# CANode.net
KiCad netlist of a schematic drawn in EAGLE
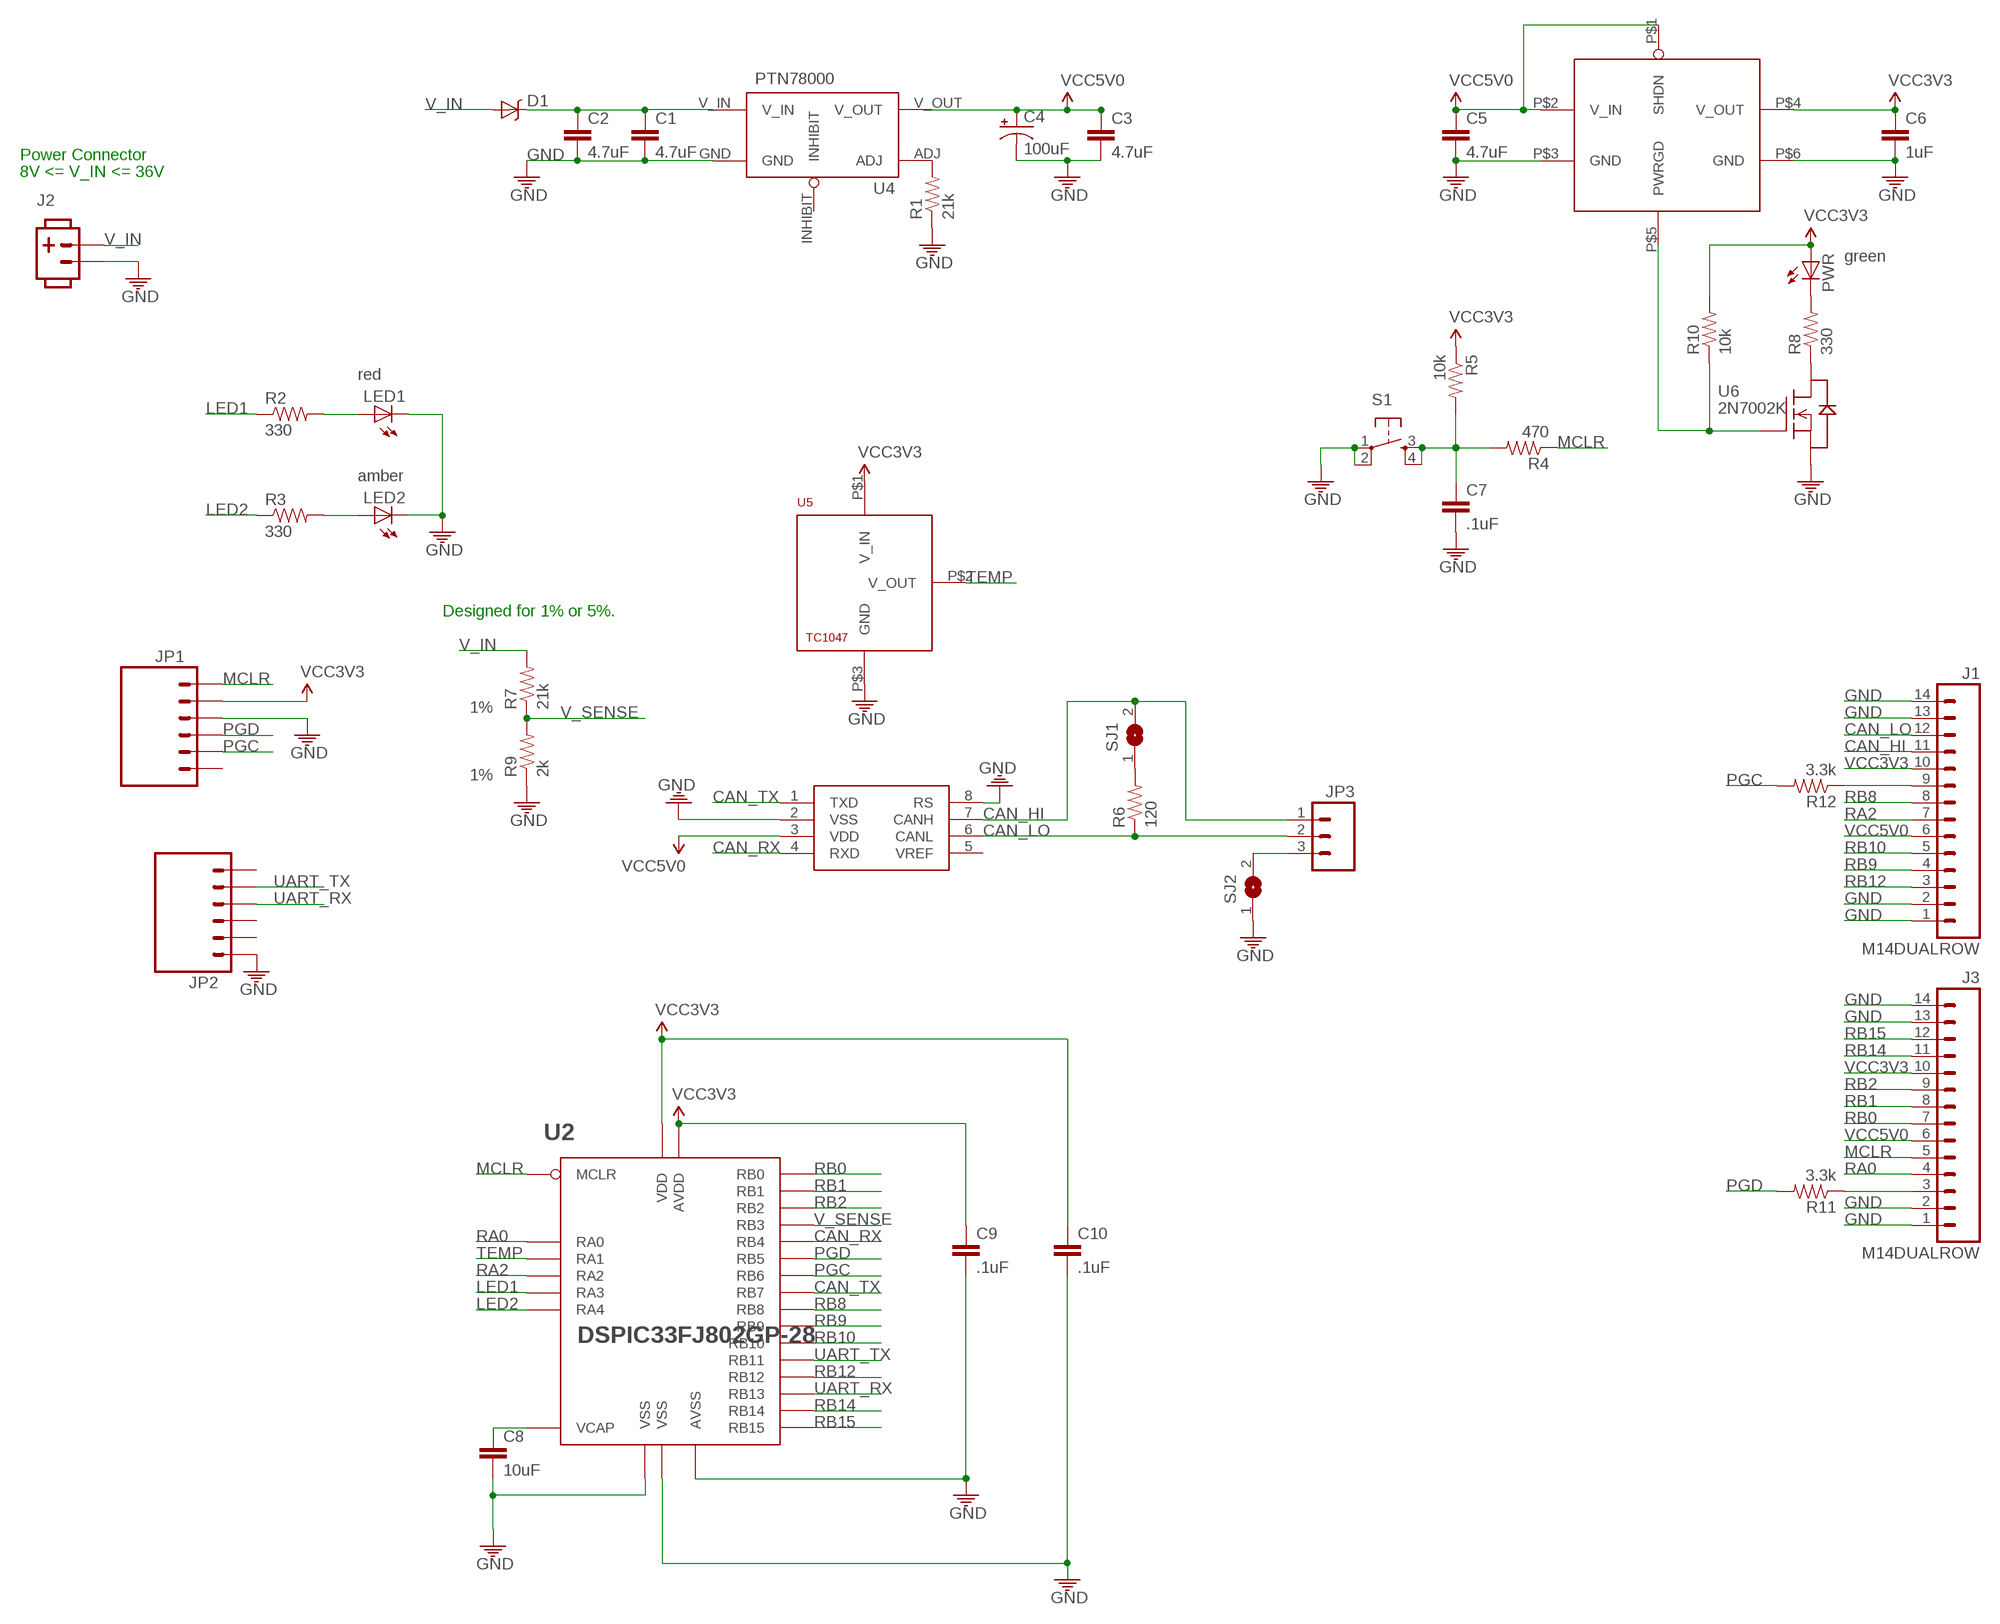
[diagram p0: schematic, sheet 1]

(export (version "E")
  (design (tool "Eeschema 10.0.6"))
  (components
    (comp (ref "C1")
      (value "4.7uF")
      (footprint "eagle-import:1206")
      (libsource (lib "eagle-import") (part "CAP1206"))
    )
    (comp (ref "C2")
      (value "4.7uF")
      (footprint "eagle-import:1206")
      (libsource (lib "eagle-import") (part "CAP1206"))
    )
    (comp (ref "C3")
      (value "4.7uF")
      (footprint "eagle-import:1206")
      (libsource (lib "eagle-import") (part "CAP1206"))
    )
    (comp (ref "C4")
      (value "100uF")
      (footprint "eagle-import:CPOL-RADIAL-100UF-25V")
      (libsource (lib "eagle-import") (part "CAP_POLPTH1"))
    )
    (comp (ref "C5")
      (value "4.7uF")
      (footprint "eagle-import:1206")
      (libsource (lib "eagle-import") (part "CAP1206"))
    )
    (comp (ref "C6")
      (value "1uF")
      (footprint "eagle-import:1206")
      (libsource (lib "eagle-import") (part "CAP1206"))
    )
    (comp (ref "C7")
      (value ".1uF")
      (footprint "eagle-import:1206")
      (libsource (lib "eagle-import") (part "CAP1206"))
    )
    (comp (ref "C8")
      (value "10uF")
      (footprint "eagle-import:1206")
      (libsource (lib "eagle-import") (part "CAP1206"))
    )
    (comp (ref "C9")
      (value ".1uF")
      (footprint "eagle-import:1206")
      (libsource (lib "eagle-import") (part "CAP1206"))
    )
    (comp (ref "C10")
      (value ".1uF")
      (footprint "eagle-import:1206")
      (libsource (lib "eagle-import") (part "CAP1206"))
    )
    (comp (ref "D1")
      (value "DIODE-SCHOTTKY240A")
      (footprint "eagle-import:SMA-DIODE-B240A")
      (libsource (lib "eagle-import") (part "DIODE-SCHOTTKY240A"))
    )
    (comp (ref "J1")
      (value "M14DUALROW")
      (footprint "eagle-import:2X7")
      (libsource (lib "eagle-import") (part "M14DUALROW"))
    )
    (comp (ref "J2")
      (value "POW_CONNECTMALE-RA")
      (footprint "eagle-import:SOCKET-MALE_RA-3.96MM-2")
      (libsource (lib "eagle-import") (part "POW_CONNECTMALE-RA"))
    )
    (comp (ref "J3")
      (value "M14DUALROW")
      (footprint "eagle-import:2X7")
      (libsource (lib "eagle-import") (part "M14DUALROW"))
    )
    (comp (ref "JP1")
      (value "M06RA_LOCK")
      (footprint "eagle-import:MOLEX-1X6-RA_LOCK")
      (libsource (lib "eagle-import") (part "M06RA_LOCK"))
    )
    (comp (ref "JP2")
      (value "M06LOCK")
      (footprint "eagle-import:1X06_LOCK")
      (libsource (lib "eagle-import") (part "CMPE118lib_M06LOCK"))
    )
    (comp (ref "JP3")
      (value "M03LOCK")
      (footprint "eagle-import:1X03_LOCK")
      (libsource (lib "eagle-import") (part "M03LOCK"))
    )
    (comp (ref "LED1")
      (value "LED1206")
      (footprint "eagle-import:LED-1206")
      (fields (field (name "COLOR") "red"))
      (libsource (lib "eagle-import") (part "LED1206"))
    )
    (comp (ref "LED2")
      (value "LED1206")
      (footprint "eagle-import:LED-1206")
      (fields (field (name "COLOR") "amber"))
      (libsource (lib "eagle-import") (part "LED1206"))
    )
    (comp (ref "PWR")
      (value "LED1206")
      (footprint "eagle-import:LED-1206")
      (fields (field (name "COLOR") "green"))
      (libsource (lib "eagle-import") (part "LED1206"))
    )
    (comp (ref "R1")
      (value "21k")
      (footprint "eagle-import:0805")
      (libsource (lib "eagle-import") (part "RESISTOR0805-RES"))
    )
    (comp (ref "R2")
      (value "330")
      (footprint "eagle-import:0805")
      (libsource (lib "eagle-import") (part "RESISTOR0805-RES"))
    )
    (comp (ref "R3")
      (value "330")
      (footprint "eagle-import:0805")
      (libsource (lib "eagle-import") (part "RESISTOR0805-RES"))
    )
    (comp (ref "R4")
      (value "470")
      (footprint "eagle-import:0805")
      (libsource (lib "eagle-import") (part "RESISTOR0805-RES"))
    )
    (comp (ref "R5")
      (value "10k")
      (footprint "eagle-import:0805")
      (libsource (lib "eagle-import") (part "RESISTOR0805-RES"))
    )
    (comp (ref "R6")
      (value "120")
      (footprint "eagle-import:0805")
      (libsource (lib "eagle-import") (part "RESISTOR0805-RES"))
    )
    (comp (ref "R7")
      (value "21k")
      (footprint "eagle-import:0805")
      (fields (field (name "PRECISION") "1%"))
      (libsource (lib "eagle-import") (part "RESISTOR0805-RES"))
    )
    (comp (ref "R8")
      (value "330")
      (footprint "eagle-import:0805")
      (libsource (lib "eagle-import") (part "RESISTOR0805-RES"))
    )
    (comp (ref "R9")
      (value "2k")
      (footprint "eagle-import:0805")
      (fields (field (name "PRECISION") "1%"))
      (libsource (lib "eagle-import") (part "RESISTOR0805-RES"))
    )
    (comp (ref "R10")
      (value "10k")
      (footprint "eagle-import:0805")
      (libsource (lib "eagle-import") (part "RESISTOR0805-RES"))
    )
    (comp (ref "R11")
      (value "3.3k")
      (footprint "eagle-import:0805")
      (libsource (lib "eagle-import") (part "RESISTOR0805-RES"))
    )
    (comp (ref "R12")
      (value "3.3k")
      (footprint "eagle-import:0805")
      (libsource (lib "eagle-import") (part "RESISTOR0805-RES"))
    )
    (comp (ref "S1")
      (value "TAC_SWITCHPTH")
      (footprint "eagle-import:B3F-1020")
      (libsource (lib "eagle-import") (part "TAC_SWITCHPTH"))
    )
    (comp (ref "SJ1") (value "SJ") (footprint "eagle-import:SJ") (libsource (lib "eagle-import") (part "SJ")))
    (comp (ref "SJ2") (value "SJ") (footprint "eagle-import:SJ") (libsource (lib "eagle-import") (part "SJ")))
    (comp (ref "U1")
      (value "MCP2551")
      (footprint "eagle-import:SO08")
      (libsource (lib "eagle-import") (part "MCP2551"))
    )
    (comp (ref "U2")
      (value "DSPIC33FJ802GP-28")
      (footprint "eagle-import:SOIC28-W")
      (libsource (lib "eagle-import") (part "DSPIC33FJ802GP-28"))
    )
    (comp (ref "U3")
      (value "MCP1826")
      (footprint "eagle-import:SOT223-5")
      (libsource (lib "eagle-import") (part "MCP1826"))
    )
    (comp (ref "U4")
      (value "PTN78000")
      (footprint "eagle-import:PTN78000")
      (libsource (lib "eagle-import") (part "PTN78000THROUGH-HOLE"))
    )
    (comp (ref "U5")
      (value "TC1047")
      (footprint "eagle-import:SOT-23B")
      (libsource (lib "eagle-import") (part "TC1047"))
    )
    (comp (ref "U6")
      (value "2N7002K")
      (footprint "eagle-import:SOT23-3")
      (libsource (lib "eagle-import") (part "2N7002K"))
    )
  )
  (nets
    (net (code "1") (name "/CAN_HI") (class "Default")
      (node (ref "J1") (pin "11") (pinfunction "11_11") (pintype "passive"))
      (node (ref "JP3") (pin "1") (pinfunction "1_1") (pintype "passive"))
      (node (ref "SJ1") (pin "2") (pinfunction "2_2") (pintype "passive"))
      (node (ref "U1") (pin "7") (pinfunction "CANH_7") (pintype "bidirectional"))
    )
    (net (code "2") (name "/CAN_LO") (class "Default")
      (node (ref "J1") (pin "12") (pinfunction "12_12") (pintype "passive"))
      (node (ref "JP3") (pin "2") (pinfunction "2_2") (pintype "passive"))
      (node (ref "R6") (pin "1") (pinfunction "1_1") (pintype "passive"))
      (node (ref "U1") (pin "6") (pinfunction "CANL_6") (pintype "bidirectional"))
    )
    (net (code "3") (name "/CAN_RX") (class "Default")
      (node (ref "U1") (pin "4") (pinfunction "RXD_4") (pintype "bidirectional"))
      (node (ref "U2") (pin "P$11") (pinfunction "RB4_P$11") (pintype "bidirectional"))
    )
    (net (code "4") (name "/CAN_TX") (class "Default")
      (node (ref "U1") (pin "1") (pinfunction "TXD_1") (pintype "bidirectional"))
      (node (ref "U2") (pin "P$16") (pinfunction "RB7_P$16") (pintype "bidirectional"))
    )
    (net (code "5") (name "/LED1") (class "Default")
      (node (ref "R2") (pin "1") (pinfunction "1_1") (pintype "passive"))
      (node (ref "U2") (pin "P$10") (pinfunction "RA3_P$10") (pintype "bidirectional"))
    )
    (net (code "6") (name "/LED2") (class "Default")
      (node (ref "R3") (pin "1") (pinfunction "1_1") (pintype "passive"))
      (node (ref "U2") (pin "P$12") (pinfunction "RA4_P$12") (pintype "bidirectional"))
    )
    (net (code "7") (name "/MCLR") (class "Default")
      (node (ref "J3") (pin "5") (pinfunction "5_5") (pintype "passive"))
      (node (ref "JP1") (pin "1") (pinfunction "1_1") (pintype "passive"))
      (node (ref "R4") (pin "1") (pinfunction "1_1") (pintype "passive"))
      (node (ref "U2") (pin "P$1") (pinfunction "MCLR_P$1") (pintype "bidirectional"))
    )
    (net (code "8") (name "/PGC") (class "Default")
      (node (ref "JP1") (pin "5") (pinfunction "5_5") (pintype "passive"))
      (node (ref "R12") (pin "2") (pinfunction "2_2") (pintype "passive"))
      (node (ref "U2") (pin "P$15") (pinfunction "RB6_P$15") (pintype "bidirectional"))
    )
    (net (code "9") (name "/PGD") (class "Default")
      (node (ref "JP1") (pin "4") (pinfunction "4_4") (pintype "passive"))
      (node (ref "R11") (pin "2") (pinfunction "2_2") (pintype "passive"))
      (node (ref "U2") (pin "P$14") (pinfunction "RB5_P$14") (pintype "bidirectional"))
    )
    (net (code "10") (name "/RA0") (class "Default")
      (node (ref "J3") (pin "4") (pinfunction "4_4") (pintype "passive"))
      (node (ref "U2") (pin "P$2") (pinfunction "RA0_P$2") (pintype "bidirectional"))
    )
    (net (code "11") (name "/RA2") (class "Default")
      (node (ref "J1") (pin "7") (pinfunction "7_7") (pintype "passive"))
      (node (ref "U2") (pin "P$9") (pinfunction "RA2_P$9") (pintype "bidirectional"))
    )
    (net (code "12") (name "/RB0") (class "Default")
      (node (ref "J3") (pin "7") (pinfunction "7_7") (pintype "passive"))
      (node (ref "U2") (pin "P$4") (pinfunction "RB0_P$4") (pintype "bidirectional"))
    )
    (net (code "13") (name "/RB1") (class "Default")
      (node (ref "J3") (pin "8") (pinfunction "8_8") (pintype "passive"))
      (node (ref "U2") (pin "P$5") (pinfunction "RB1_P$5") (pintype "bidirectional"))
    )
    (net (code "14") (name "/RB2") (class "Default")
      (node (ref "J3") (pin "9") (pinfunction "9_9") (pintype "passive"))
      (node (ref "U2") (pin "P$6") (pinfunction "RB2_P$6") (pintype "bidirectional"))
    )
    (net (code "15") (name "/RB8") (class "Default")
      (node (ref "J1") (pin "8") (pinfunction "8_8") (pintype "passive"))
      (node (ref "U2") (pin "P$17") (pinfunction "RB8_P$17") (pintype "bidirectional"))
    )
    (net (code "16") (name "/RB9") (class "Default")
      (node (ref "J1") (pin "4") (pinfunction "4_4") (pintype "passive"))
      (node (ref "U2") (pin "P$18") (pinfunction "RB9_P$18") (pintype "bidirectional"))
    )
    (net (code "17") (name "/RB10") (class "Default")
      (node (ref "J1") (pin "5") (pinfunction "5_5") (pintype "passive"))
      (node (ref "U2") (pin "P$21") (pinfunction "RB10_P$21") (pintype "bidirectional"))
    )
    (net (code "18") (name "/RB12") (class "Default")
      (node (ref "J1") (pin "3") (pinfunction "3_3") (pintype "passive"))
      (node (ref "U2") (pin "P$23") (pinfunction "RB12_P$23") (pintype "bidirectional"))
    )
    (net (code "19") (name "/RB14") (class "Default")
      (node (ref "J3") (pin "11") (pinfunction "11_11") (pintype "passive"))
      (node (ref "U2") (pin "P$25") (pinfunction "RB14_P$25") (pintype "bidirectional"))
    )
    (net (code "20") (name "/RB15") (class "Default")
      (node (ref "J3") (pin "12") (pinfunction "12_12") (pintype "passive"))
      (node (ref "U2") (pin "P$26") (pinfunction "RB15_P$26") (pintype "bidirectional"))
    )
    (net (code "21") (name "/TEMP") (class "Default")
      (node (ref "U2") (pin "P$3") (pinfunction "RA1_P$3") (pintype "bidirectional"))
      (node (ref "U5") (pin "P$2") (pinfunction "V_OUT_P$2") (pintype "output"))
    )
    (net (code "22") (name "/UART_RX") (class "Default")
      (node (ref "JP2") (pin "4") (pinfunction "4_4") (pintype "passive"))
      (node (ref "U2") (pin "P$24") (pinfunction "RB13_P$24") (pintype "bidirectional"))
    )
    (net (code "23") (name "/UART_TX") (class "Default")
      (node (ref "JP2") (pin "5") (pinfunction "5_5") (pintype "passive"))
      (node (ref "U2") (pin "P$22") (pinfunction "RB11_P$22") (pintype "bidirectional"))
    )
    (net (code "24") (name "/V_IN") (class "Default")
      (node (ref "D1") (pin "A") (pinfunction "A_A") (pintype "passive"))
      (node (ref "J2") (pin "1") (pinfunction "1_1") (pintype "passive"))
      (node (ref "R7") (pin "2") (pinfunction "2_2") (pintype "passive"))
    )
    (net (code "25") (name "/V_SENSE") (class "Default")
      (node (ref "R7") (pin "1") (pinfunction "1_1") (pintype "passive"))
      (node (ref "R9") (pin "2") (pinfunction "2_2") (pintype "passive"))
      (node (ref "U2") (pin "P$7") (pinfunction "RB3_P$7") (pintype "bidirectional"))
    )
    (net (code "26") (name "GND") (class "Default")
      (node (ref "C1") (pin "2") (pinfunction "2_2") (pintype "passive"))
      (node (ref "C10") (pin "2") (pinfunction "2_2") (pintype "passive"))
      (node (ref "C2") (pin "2") (pinfunction "2_2") (pintype "passive"))
      (node (ref "C3") (pin "2") (pinfunction "2_2") (pintype "passive"))
      (node (ref "C4") (pin "2") (pinfunction "-_2") (pintype "passive"))
      (node (ref "C5") (pin "2") (pinfunction "2_2") (pintype "passive"))
      (node (ref "C6") (pin "2") (pinfunction "2_2") (pintype "passive"))
      (node (ref "C7") (pin "2") (pinfunction "2_2") (pintype "passive"))
      (node (ref "C8") (pin "2") (pinfunction "2_2") (pintype "passive"))
      (node (ref "C9") (pin "2") (pinfunction "2_2") (pintype "passive"))
      (node (ref "J1") (pin "1") (pinfunction "1_1") (pintype "passive"))
      (node (ref "J1") (pin "13") (pinfunction "13_13") (pintype "passive"))
      (node (ref "J1") (pin "14") (pinfunction "14_14") (pintype "passive"))
      (node (ref "J1") (pin "2") (pinfunction "2_2") (pintype "passive"))
      (node (ref "J2") (pin "2") (pinfunction "2_2") (pintype "passive"))
      (node (ref "J3") (pin "1") (pinfunction "1_1") (pintype "passive"))
      (node (ref "J3") (pin "13") (pinfunction "13_13") (pintype "passive"))
      (node (ref "J3") (pin "14") (pinfunction "14_14") (pintype "passive"))
      (node (ref "J3") (pin "2") (pinfunction "2_2") (pintype "passive"))
      (node (ref "JP1") (pin "3") (pinfunction "3_3") (pintype "passive"))
      (node (ref "JP2") (pin "1") (pinfunction "1_1") (pintype "passive"))
      (node (ref "LED1") (pin "C") (pinfunction "C_C") (pintype "passive"))
      (node (ref "LED2") (pin "C") (pinfunction "C_C") (pintype "passive"))
      (node (ref "R1") (pin "1") (pinfunction "1_1") (pintype "passive"))
      (node (ref "R9") (pin "1") (pinfunction "1_1") (pintype "passive"))
      (node (ref "S1") (pin "1") (pinfunction "1_1") (pintype "passive"))
      (node (ref "S1") (pin "2") (pinfunction "2_2") (pintype "passive"))
      (node (ref "SJ2") (pin "1") (pinfunction "1_1") (pintype "passive"))
      (node (ref "U1") (pin "2") (pinfunction "VSS_2") (pintype "bidirectional"))
      (node (ref "U1") (pin "8") (pinfunction "RS_8") (pintype "bidirectional"))
      (node (ref "U2") (pin "P$19") (pinfunction "VSS_P$19") (pintype "power_in"))
      (node (ref "U2") (pin "P$27") (pinfunction "AVSS_P$27") (pintype "input"))
      (node (ref "U2") (pin "P$8") (pinfunction "VSS_P$8") (pintype "power_in"))
      (node (ref "U3") (pin "P$3") (pinfunction "GND_P$3") (pintype "power_in"))
      (node (ref "U3") (pin "P$6") (pinfunction "GND_P$6") (pintype "power_in"))
      (node (ref "U4") (pin "GND") (pinfunction "GND_GND") (pintype "power_in"))
      (node (ref "U5") (pin "P$3") (pinfunction "GND_P$3") (pintype "power_in"))
      (node (ref "U6") (pin "2") (pinfunction "S_2") (pintype "passive"))
    )
    (net (code "27") (name "Net-(C1-Pad1)") (class "Default")
      (node (ref "C1") (pin "1") (pinfunction "1_1") (pintype "passive"))
      (node (ref "C2") (pin "1") (pinfunction "1_1") (pintype "passive"))
      (node (ref "D1") (pin "C") (pinfunction "C_C") (pintype "passive"))
      (node (ref "U4") (pin "V_IN") (pinfunction "V_IN_V_IN") (pintype "power_in"))
    )
    (net (code "28") (name "Net-(C7-Pad1)") (class "Default")
      (node (ref "C7") (pin "1") (pinfunction "1_1") (pintype "passive"))
      (node (ref "R4") (pin "2") (pinfunction "2_2") (pintype "passive"))
      (node (ref "R5") (pin "2") (pinfunction "2_2") (pintype "passive"))
      (node (ref "S1") (pin "3") (pinfunction "3_3") (pintype "passive"))
      (node (ref "S1") (pin "4") (pinfunction "4_4") (pintype "passive"))
    )
    (net (code "29") (name "Net-(J1-Pad9)") (class "Default")
      (node (ref "J1") (pin "9") (pinfunction "9_9") (pintype "passive"))
      (node (ref "R12") (pin "1") (pinfunction "1_1") (pintype "passive"))
    )
    (net (code "30") (name "Net-(J3-Pad3)") (class "Default")
      (node (ref "J3") (pin "3") (pinfunction "3_3") (pintype "passive"))
      (node (ref "R11") (pin "1") (pinfunction "1_1") (pintype "passive"))
    )
    (net (code "31") (name "Net-(JP3-Pad3)") (class "Default")
      (node (ref "JP3") (pin "3") (pinfunction "3_3") (pintype "passive"))
      (node (ref "SJ2") (pin "2") (pinfunction "2_2") (pintype "passive"))
    )
    (net (code "32") (name "Net-(LED1-PadA)") (class "Default")
      (node (ref "LED1") (pin "A") (pinfunction "A_A") (pintype "passive"))
      (node (ref "R2") (pin "2") (pinfunction "2_2") (pintype "passive"))
    )
    (net (code "33") (name "Net-(LED2-PadA)") (class "Default")
      (node (ref "LED2") (pin "A") (pinfunction "A_A") (pintype "passive"))
      (node (ref "R3") (pin "2") (pinfunction "2_2") (pintype "passive"))
    )
    (net (code "34") (name "Net-(PWR-PadC)") (class "Default")
      (node (ref "PWR") (pin "C") (pinfunction "C_C") (pintype "passive"))
      (node (ref "R8") (pin "2") (pinfunction "2_2") (pintype "passive"))
    )
    (net (code "35") (name "Net-(R1-Pad2)") (class "Default")
      (node (ref "R1") (pin "2") (pinfunction "2_2") (pintype "passive"))
      (node (ref "U4") (pin "ADJ") (pinfunction "ADJ_ADJ") (pintype "input"))
    )
    (net (code "36") (name "Net-(R6-Pad2)") (class "Default")
      (node (ref "R6") (pin "2") (pinfunction "2_2") (pintype "passive"))
      (node (ref "SJ1") (pin "1") (pinfunction "1_1") (pintype "passive"))
    )
    (net (code "37") (name "Net-(U2-VCAP)") (class "Default")
      (node (ref "C8") (pin "1") (pinfunction "1_1") (pintype "passive"))
      (node (ref "U2") (pin "P$20") (pinfunction "VCAP_P$20") (pintype "input"))
    )
    (net (code "38") (name "Net-(U3-PWRGD)") (class "Default")
      (node (ref "R10") (pin "1") (pinfunction "1_1") (pintype "passive"))
      (node (ref "U3") (pin "P$5") (pinfunction "PWRGD_P$5") (pintype "open_collector"))
      (node (ref "U6") (pin "1") (pinfunction "G_1") (pintype "passive"))
    )
    (net (code "39") (name "Net-(U6-D)") (class "Default")
      (node (ref "R8") (pin "1") (pinfunction "1_1") (pintype "passive"))
      (node (ref "U6") (pin "3") (pinfunction "D_3") (pintype "passive"))
    )
    (net (code "40") (name "VCC3V3") (class "Default")
      (node (ref "C10") (pin "1") (pinfunction "1_1") (pintype "passive"))
      (node (ref "C6") (pin "1") (pinfunction "1_1") (pintype "passive"))
      (node (ref "C9") (pin "1") (pinfunction "1_1") (pintype "passive"))
      (node (ref "J1") (pin "10") (pinfunction "10_10") (pintype "passive"))
      (node (ref "J3") (pin "10") (pinfunction "10_10") (pintype "passive"))
      (node (ref "JP1") (pin "2") (pinfunction "2_2") (pintype "passive"))
      (node (ref "PWR") (pin "A") (pinfunction "A_A") (pintype "passive"))
      (node (ref "R10") (pin "2") (pinfunction "2_2") (pintype "passive"))
      (node (ref "R5") (pin "1") (pinfunction "1_1") (pintype "passive"))
      (node (ref "U2") (pin "P$13") (pinfunction "VDD_P$13") (pintype "power_in"))
      (node (ref "U2") (pin "P$28") (pinfunction "AVDD_P$28") (pintype "input"))
      (node (ref "U3") (pin "P$4") (pinfunction "V_OUT_P$4") (pintype "output"))
      (node (ref "U5") (pin "P$1") (pinfunction "V_IN_P$1") (pintype "power_in"))
    )
    (net (code "41") (name "VCC5V0") (class "Default")
      (node (ref "C3") (pin "1") (pinfunction "1_1") (pintype "passive"))
      (node (ref "C4") (pin "1") (pinfunction "+_1") (pintype "passive"))
      (node (ref "C5") (pin "1") (pinfunction "1_1") (pintype "passive"))
      (node (ref "J1") (pin "6") (pinfunction "6_6") (pintype "passive"))
      (node (ref "J3") (pin "6") (pinfunction "6_6") (pintype "passive"))
      (node (ref "U1") (pin "3") (pinfunction "VDD_3") (pintype "bidirectional"))
      (node (ref "U3") (pin "P$1") (pinfunction "SHDN_P$1") (pintype "input"))
      (node (ref "U3") (pin "P$2") (pinfunction "V_IN_P$2") (pintype "power_in"))
      (node (ref "U4") (pin "V_OUT") (pinfunction "V_OUT_V_OUT") (pintype "output"))
    )
    (net (code "42") (name "unconnected-(JP1-Pad6)") (class "Default")
      (node (ref "JP1") (pin "6") (pinfunction "6_6") (pintype "passive"))
    )
    (net (code "43") (name "unconnected-(JP2-Pad2)") (class "Default")
      (node (ref "JP2") (pin "2") (pinfunction "2_2") (pintype "passive"))
    )
    (net (code "44") (name "unconnected-(JP2-Pad3)") (class "Default")
      (node (ref "JP2") (pin "3") (pinfunction "3_3") (pintype "passive"))
    )
    (net (code "45") (name "unconnected-(JP2-Pad6)") (class "Default")
      (node (ref "JP2") (pin "6") (pinfunction "6_6") (pintype "passive"))
    )
    (net (code "46") (name "unconnected-(U1-VREF-Pad5)") (class "Default")
      (node (ref "U1") (pin "5") (pinfunction "VREF_5") (pintype "bidirectional"))
    )
    (net (code "47") (name "unconnected-(U4-PadINHIBIT)") (class "Default")
      (node (ref "U4") (pin "INHIBIT") (pinfunction "INHIBIT_INHIBIT") (pintype "input"))
    )
  )
)
